# HIH6.net
KiCad netlist of a schematic drawn in EAGLE
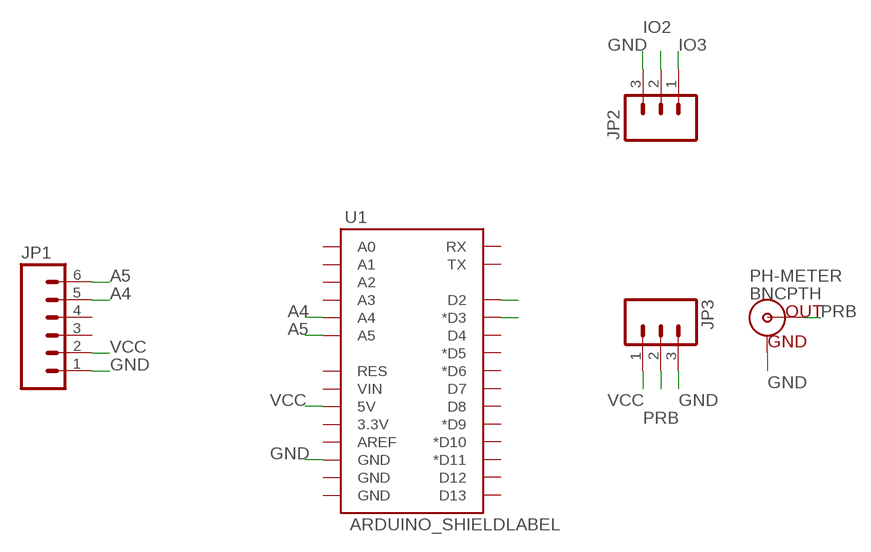
[diagram p0: schematic, sheet 1]

(export (version "E")
  (design (tool "Eeschema 10.0.6"))
  (components
    (comp (ref "JP1")
      (value "M06LONGPADS")
      (footprint "eagle-import:1X06_LONGPADS")
      (libsource (lib "eagle-import") (part "M06LONGPADS"))
    )
    (comp (ref "JP2")
      (value "M03LONGPADS")
      (footprint "eagle-import:1X03_LONGPADS")
      (libsource (lib "eagle-import") (part "M03LONGPADS"))
    )
    (comp (ref "JP3")
      (value "M03LONGPADS")
      (footprint "eagle-import:1X03_LONGPADS")
      (libsource (lib "eagle-import") (part "M03LONGPADS"))
    )
    (comp (ref "PH-METER")
      (value "BNCPTH")
      (footprint "eagle-import:BNC")
      (libsource (lib "eagle-import") (part "BNCPTH"))
    )
    (comp (ref "U1")
      (value "ARDUINO_SHIELDLABEL")
      (footprint "eagle-import:DUEMILANOVE_SHIELD")
      (libsource (lib "eagle-import") (part "ARDUINO_SHIELDLABEL"))
    )
  )
  (nets
    (net (code "1") (name "/A4") (class "Default")
      (node (ref "JP1") (pin "5") (pinfunction "5_5") (pintype "passive"))
      (node (ref "U1") (pin "A4") (pinfunction "A4_A4") (pintype "bidirectional"))
    )
    (net (code "2") (name "/A5") (class "Default")
      (node (ref "JP1") (pin "6") (pinfunction "6_6") (pintype "passive"))
      (node (ref "U1") (pin "A5") (pinfunction "A5_A5") (pintype "bidirectional"))
    )
    (net (code "3") (name "/GND") (class "Default")
      (node (ref "JP1") (pin "1") (pinfunction "1_1") (pintype "passive"))
      (node (ref "JP2") (pin "3") (pinfunction "3_3") (pintype "passive"))
      (node (ref "JP3") (pin "3") (pinfunction "3_3") (pintype "passive"))
      (node (ref "PH-METER") (pin "GND") (pinfunction "GND_GND") (pintype "bidirectional"))
      (node (ref "U1") (pin "GND@2") (pinfunction "GND_GND@2") (pintype "bidirectional"))
    )
    (net (code "4") (name "/IO2") (class "Default")
      (node (ref "JP2") (pin "2") (pinfunction "2_2") (pintype "passive"))
      (node (ref "U1") (pin "D2") (pinfunction "D2_D2") (pintype "bidirectional"))
    )
    (net (code "5") (name "/IO3") (class "Default")
      (node (ref "JP2") (pin "1") (pinfunction "1_1") (pintype "passive"))
      (node (ref "U1") (pin "D3") (pinfunction "*D3_D3") (pintype "bidirectional"))
    )
    (net (code "6") (name "/PRB") (class "Default")
      (node (ref "JP3") (pin "2") (pinfunction "2_2") (pintype "passive"))
      (node (ref "PH-METER") (pin "S") (pinfunction "OUT_S") (pintype "bidirectional"))
    )
    (net (code "7") (name "/VCC") (class "Default")
      (node (ref "JP1") (pin "2") (pinfunction "2_2") (pintype "passive"))
      (node (ref "JP3") (pin "1") (pinfunction "1_1") (pintype "passive"))
      (node (ref "U1") (pin "5V") (pinfunction "5V_5V") (pintype "bidirectional"))
    )
    (net (code "8") (name "unconnected-(JP1-Pad3)") (class "Default")
      (node (ref "JP1") (pin "3") (pinfunction "3_3") (pintype "passive"))
    )
    (net (code "9") (name "unconnected-(JP1-Pad4)") (class "Default")
      (node (ref "JP1") (pin "4") (pinfunction "4_4") (pintype "passive"))
    )
    (net (code "10") (name "unconnected-(U1-*D5-PadD5)") (class "Default")
      (node (ref "U1") (pin "D5") (pinfunction "*D5_D5") (pintype "bidirectional"))
    )
    (net (code "11") (name "unconnected-(U1-*D6-PadD6)") (class "Default")
      (node (ref "U1") (pin "D6") (pinfunction "*D6_D6") (pintype "bidirectional"))
    )
    (net (code "12") (name "unconnected-(U1-*D9-PadD9)") (class "Default")
      (node (ref "U1") (pin "D9") (pinfunction "*D9_D9") (pintype "bidirectional"))
    )
    (net (code "13") (name "unconnected-(U1-*D10-PadD10)") (class "Default")
      (node (ref "U1") (pin "D10") (pinfunction "*D10_D10") (pintype "bidirectional"))
    )
    (net (code "14") (name "unconnected-(U1-*D11-PadD11)") (class "Default")
      (node (ref "U1") (pin "D11") (pinfunction "*D11_D11") (pintype "bidirectional"))
    )
    (net (code "15") (name "unconnected-(U1-GND-PadGND@0)") (class "Default")
      (node (ref "U1") (pin "GND@0") (pinfunction "GND_GND@0") (pintype "bidirectional"))
    )
    (net (code "16") (name "unconnected-(U1-GND-PadGND@1)") (class "Default")
      (node (ref "U1") (pin "GND@1") (pinfunction "GND_GND@1") (pintype "bidirectional"))
    )
    (net (code "17") (name "unconnected-(U1-Pad3.3V)") (class "Default")
      (node (ref "U1") (pin "3.3V") (pinfunction "3.3V_3.3V") (pintype "bidirectional"))
    )
    (net (code "18") (name "unconnected-(U1-PadA0)") (class "Default")
      (node (ref "U1") (pin "A0") (pinfunction "A0_A0") (pintype "bidirectional"))
    )
    (net (code "19") (name "unconnected-(U1-PadA1)") (class "Default")
      (node (ref "U1") (pin "A1") (pinfunction "A1_A1") (pintype "bidirectional"))
    )
    (net (code "20") (name "unconnected-(U1-PadA2)") (class "Default")
      (node (ref "U1") (pin "A2") (pinfunction "A2_A2") (pintype "bidirectional"))
    )
    (net (code "21") (name "unconnected-(U1-PadA3)") (class "Default")
      (node (ref "U1") (pin "A3") (pinfunction "A3_A3") (pintype "bidirectional"))
    )
    (net (code "22") (name "unconnected-(U1-PadAREF)") (class "Default")
      (node (ref "U1") (pin "AREF") (pinfunction "AREF_AREF") (pintype "bidirectional"))
    )
    (net (code "23") (name "unconnected-(U1-PadD4)") (class "Default")
      (node (ref "U1") (pin "D4") (pinfunction "D4_D4") (pintype "bidirectional"))
    )
    (net (code "24") (name "unconnected-(U1-PadD7)") (class "Default")
      (node (ref "U1") (pin "D7") (pinfunction "D7_D7") (pintype "bidirectional"))
    )
    (net (code "25") (name "unconnected-(U1-PadD8)") (class "Default")
      (node (ref "U1") (pin "D8") (pinfunction "D8_D8") (pintype "bidirectional"))
    )
    (net (code "26") (name "unconnected-(U1-PadD12)") (class "Default")
      (node (ref "U1") (pin "D12") (pinfunction "D12_D12") (pintype "bidirectional"))
    )
    (net (code "27") (name "unconnected-(U1-PadD13)") (class "Default")
      (node (ref "U1") (pin "D13") (pinfunction "D13_D13") (pintype "bidirectional"))
    )
    (net (code "28") (name "unconnected-(U1-PadRES)") (class "Default")
      (node (ref "U1") (pin "RES") (pinfunction "RES_RES") (pintype "bidirectional"))
    )
    (net (code "29") (name "unconnected-(U1-PadRX)") (class "Default")
      (node (ref "U1") (pin "RX") (pinfunction "RX_RX") (pintype "bidirectional"))
    )
    (net (code "30") (name "unconnected-(U1-PadTX)") (class "Default")
      (node (ref "U1") (pin "TX") (pinfunction "TX_TX") (pintype "bidirectional"))
    )
    (net (code "31") (name "unconnected-(U1-PadVIN)") (class "Default")
      (node (ref "U1") (pin "VIN") (pinfunction "VIN_VIN") (pintype "bidirectional"))
    )
  )
)
